# FNR_Controller_v1_0_-_Relay.net
KiCad netlist of a schematic drawn in EAGLE
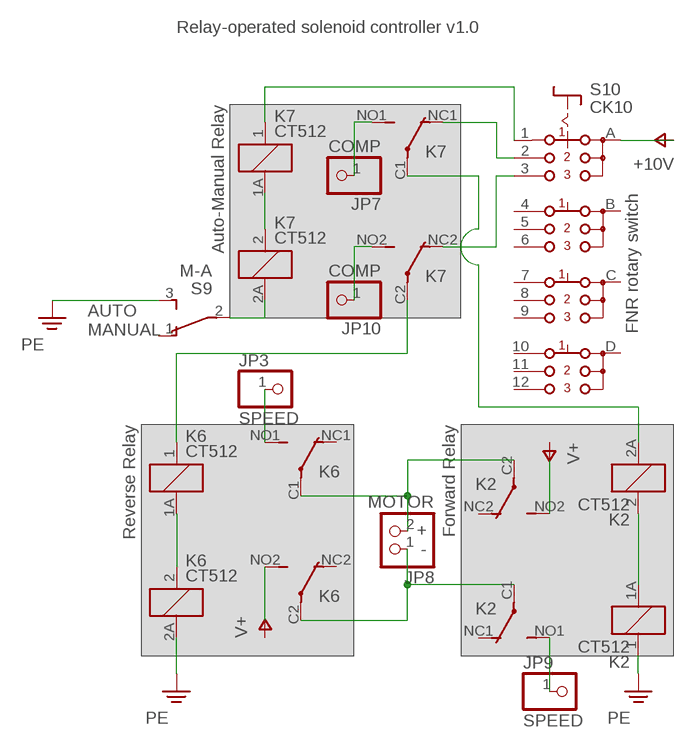
[diagram p0: schematic, sheet 1]

(export (version "E")
  (design (tool "Eeschema 10.0.6"))
  (components
    (comp (ref "JP3")
      (value "SPEED")
      (footprint "eagle-import:1X01")
      (libsource (lib "eagle-import") (part "PINHD-1X1"))
    )
    (comp (ref "JP7")
      (value "COMP")
      (footprint "eagle-import:1X01")
      (libsource (lib "eagle-import") (part "PINHD-1X1"))
    )
    (comp (ref "JP8")
      (value "MOTOR")
      (footprint "eagle-import:1X02")
      (libsource (lib "eagle-import") (part "PINHD-1X2"))
    )
    (comp (ref "JP9")
      (value "SPEED")
      (footprint "eagle-import:1X01")
      (libsource (lib "eagle-import") (part "PINHD-1X1"))
    )
    (comp (ref "JP10")
      (value "COMP")
      (footprint "eagle-import:1X01")
      (libsource (lib "eagle-import") (part "PINHD-1X1"))
    )
    (comp (ref "K2")
      (value "CT512")
      (footprint "eagle-import:CT2-TWIN")
      (libsource (lib "eagle-import") (part "CT512"))
    )
    (comp (ref "K6")
      (value "CT512")
      (footprint "eagle-import:CT2-TWIN")
      (libsource (lib "eagle-import") (part "CT512"))
    )
    (comp (ref "K7")
      (value "CT512")
      (footprint "eagle-import:CT2-TWIN")
      (libsource (lib "eagle-import") (part "CT512"))
    )
    (comp (ref "S9")
      (value "M-A")
      (footprint "eagle-import:TL3XPO")
      (libsource (lib "eagle-import") (part "TL36PO"))
    )
    (comp (ref "S10")
      (value "CK10")
      (footprint "eagle-import:CK10")
      (libsource (lib "eagle-import") (part "CK10"))
    )
  )
  (nets
    (net (code "1") (name "+10V") (class "Default")
      (node (ref "S10") (pin "A") (pinfunction "A_A") (pintype "passive"))
    )
    (net (code "2") (name "Net-(K2A-2)") (class "Default")
      (node (ref "K2") (pin "1A") (pinfunction "2_1A") (pintype "passive"))
      (node (ref "K2") (pin "2") (pinfunction "1_2") (pintype "passive"))
    )
    (net (code "3") (name "Net-(K2B-P)") (class "Default")
      (node (ref "JP8") (pin "1") (pinfunction "1_1") (pintype "passive"))
      (node (ref "K2") (pin "C1") (pinfunction "P_C1") (pintype "passive"))
      (node (ref "K6") (pin "C2") (pinfunction "P_C2") (pintype "passive"))
    )
    (net (code "4") (name "Net-(K2B-S)") (class "Default")
      (node (ref "JP9") (pin "1") (pinfunction "1_1") (pintype "passive"))
      (node (ref "K2") (pin "NO1") (pinfunction "S_NO1") (pintype "passive"))
    )
    (net (code "5") (name "Net-(K2C-2)") (class "Default")
      (node (ref "K2") (pin "2A") (pinfunction "2_2A") (pintype "passive"))
      (node (ref "K7") (pin "C1") (pinfunction "P_C1") (pintype "passive"))
    )
    (net (code "6") (name "Net-(K2D-P)") (class "Default")
      (node (ref "JP8") (pin "2") (pinfunction "2_2") (pintype "passive"))
      (node (ref "K2") (pin "C2") (pinfunction "P_C2") (pintype "passive"))
      (node (ref "K6") (pin "C1") (pinfunction "P_C1") (pintype "passive"))
    )
    (net (code "7") (name "Net-(K6A-2)") (class "Default")
      (node (ref "K6") (pin "1A") (pinfunction "2_1A") (pintype "passive"))
      (node (ref "K6") (pin "2") (pinfunction "1_2") (pintype "passive"))
    )
    (net (code "8") (name "Net-(K6B-S)") (class "Default")
      (node (ref "JP3") (pin "1") (pinfunction "1_1") (pintype "passive"))
      (node (ref "K6") (pin "NO1") (pinfunction "S_NO1") (pintype "passive"))
    )
    (net (code "9") (name "Net-(K7A-2)") (class "Default")
      (node (ref "K7") (pin "1A") (pinfunction "2_1A") (pintype "passive"))
      (node (ref "K7") (pin "2") (pinfunction "1_2") (pintype "passive"))
    )
    (net (code "10") (name "Net-(K7B-O)") (class "Default")
      (node (ref "K7") (pin "NC1") (pinfunction "O_NC1") (pintype "passive"))
      (node (ref "S10") (pin "2") (pinfunction "A2_2") (pintype "passive"))
    )
    (net (code "11") (name "Net-(K7B-S)") (class "Default")
      (node (ref "JP7") (pin "1") (pinfunction "1_1") (pintype "passive"))
      (node (ref "K7") (pin "NO1") (pinfunction "S_NO1") (pintype "passive"))
    )
    (net (code "12") (name "Net-(K7C-2)") (class "Default")
      (node (ref "K7") (pin "2A") (pinfunction "2_2A") (pintype "passive"))
      (node (ref "S9") (pin "2") (pinfunction "P_2") (pintype "passive"))
    )
    (net (code "13") (name "Net-(K7D-O)") (class "Default")
      (node (ref "K7") (pin "NC2") (pinfunction "O_NC2") (pintype "passive"))
      (node (ref "S10") (pin "3") (pinfunction "A3_3") (pintype "passive"))
    )
    (net (code "14") (name "Net-(K7D-P)") (class "Default")
      (node (ref "K6") (pin "1") (pinfunction "1_1") (pintype "passive"))
      (node (ref "K7") (pin "C2") (pinfunction "P_C2") (pintype "passive"))
    )
    (net (code "15") (name "Net-(K7D-S)") (class "Default")
      (node (ref "JP10") (pin "1") (pinfunction "1_1") (pintype "passive"))
      (node (ref "K7") (pin "NO2") (pinfunction "S_NO2") (pintype "passive"))
    )
    (net (code "16") (name "Net-(S10-A1)") (class "Default")
      (node (ref "K7") (pin "1") (pinfunction "1_1") (pintype "passive"))
      (node (ref "S10") (pin "1") (pinfunction "A1_1") (pintype "passive"))
    )
    (net (code "17") (name "PE") (class "Default")
      (node (ref "K2") (pin "1") (pinfunction "1_1") (pintype "passive"))
      (node (ref "K6") (pin "2A") (pinfunction "2_2A") (pintype "passive"))
      (node (ref "S9") (pin "3") (pinfunction "S_3") (pintype "passive"))
    )
    (net (code "19") (name "unconnected-(K2B-O-PadNC1)") (class "Default")
      (node (ref "K2") (pin "NC1") (pinfunction "O_NC1") (pintype "passive"))
    )
    (net (code "20") (name "unconnected-(K2D-O-PadNC2)") (class "Default")
      (node (ref "K2") (pin "NC2") (pinfunction "O_NC2") (pintype "passive"))
    )
    (net (code "21") (name "unconnected-(K2D-S-PadNO2)") (class "Default")
      (node (ref "K2") (pin "NO2") (pinfunction "S_NO2") (pintype "passive"))
    )
    (net (code "22") (name "unconnected-(K6B-O-PadNC1)") (class "Default")
      (node (ref "K6") (pin "NC1") (pinfunction "O_NC1") (pintype "passive"))
    )
    (net (code "23") (name "unconnected-(K6D-O-PadNC2)") (class "Default")
      (node (ref "K6") (pin "NC2") (pinfunction "O_NC2") (pintype "passive"))
    )
    (net (code "24") (name "unconnected-(K6D-S-PadNO2)") (class "Default")
      (node (ref "K6") (pin "NO2") (pinfunction "S_NO2") (pintype "passive"))
    )
    (net (code "25") (name "unconnected-(S9-O-Pad1)") (class "Default")
      (node (ref "S9") (pin "1") (pinfunction "O_1") (pintype "passive"))
    )
    (net (code "26") (name "unconnected-(S10-B1-Pad4)") (class "Default")
      (node (ref "S10") (pin "4") (pinfunction "B1_4") (pintype "passive"))
    )
    (net (code "27") (name "unconnected-(S10-B2-Pad5)") (class "Default")
      (node (ref "S10") (pin "5") (pinfunction "B2_5") (pintype "passive"))
    )
    (net (code "28") (name "unconnected-(S10-B3-Pad6)") (class "Default")
      (node (ref "S10") (pin "6") (pinfunction "B3_6") (pintype "passive"))
    )
    (net (code "29") (name "unconnected-(S10-C1-Pad7)") (class "Default")
      (node (ref "S10") (pin "7") (pinfunction "C1_7") (pintype "passive"))
    )
    (net (code "30") (name "unconnected-(S10-C2-Pad8)") (class "Default")
      (node (ref "S10") (pin "8") (pinfunction "C2_8") (pintype "passive"))
    )
    (net (code "31") (name "unconnected-(S10-C3-Pad9)") (class "Default")
      (node (ref "S10") (pin "9") (pinfunction "C3_9") (pintype "passive"))
    )
    (net (code "32") (name "unconnected-(S10-D1-Pad10)") (class "Default")
      (node (ref "S10") (pin "10") (pinfunction "D1_10") (pintype "passive"))
    )
    (net (code "33") (name "unconnected-(S10-D2-Pad11)") (class "Default")
      (node (ref "S10") (pin "11") (pinfunction "D2_11") (pintype "passive"))
    )
    (net (code "34") (name "unconnected-(S10-D3-Pad12)") (class "Default")
      (node (ref "S10") (pin "12") (pinfunction "D3_12") (pintype "passive"))
    )
    (net (code "35") (name "unconnected-(S10-PadB)") (class "Default")
      (node (ref "S10") (pin "B") (pinfunction "B_B") (pintype "passive"))
    )
    (net (code "36") (name "unconnected-(S10-PadC)") (class "Default")
      (node (ref "S10") (pin "C") (pinfunction "C_C") (pintype "passive"))
    )
    (net (code "37") (name "unconnected-(S10-PadD)") (class "Default")
      (node (ref "S10") (pin "D") (pinfunction "D_D") (pintype "passive"))
    )
  )
)
